# FPGA_Board_Top.net
KiCad netlist of a schematic drawn in Altium Designer
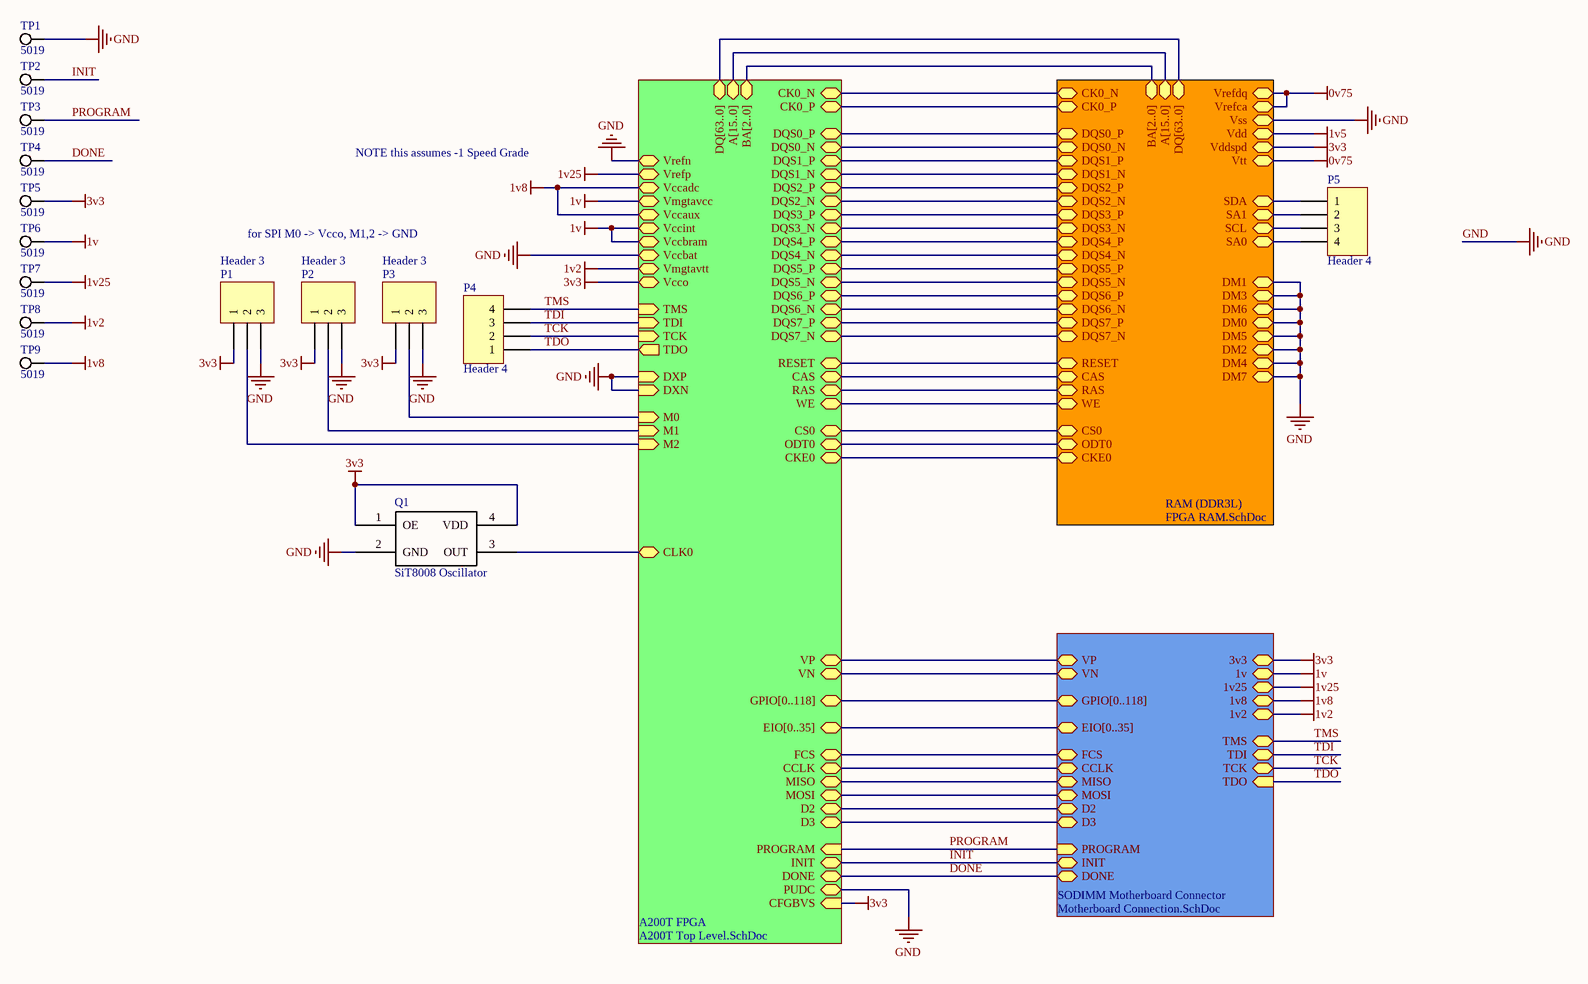
[diagram p0: FPGA Board Top.SchDoc]

(export (version "E")
  (design (tool "Eeschema 10.0.6"))
  (components
    (comp (ref "P1")
      (value "Header 3")
      (footprint "HDR1X3")
      (description "Header, 3-Pin")
      (fields (field (name "PUBLISHER") "Altium Limited"))
      (libsource (lib "Miscellaneous Connectors") (part "Header 3"))
    )
    (comp (ref "P2")
      (value "Header 3")
      (footprint "HDR1X3")
      (description "Header, 3-Pin")
      (fields (field (name "PUBLISHER") "Altium Limited"))
      (libsource (lib "Miscellaneous Connectors") (part "Header 3"))
    )
    (comp (ref "P3")
      (value "Header 3")
      (footprint "HDR1X3")
      (description "Header, 3-Pin")
      (fields (field (name "PUBLISHER") "Altium Limited"))
      (libsource (lib "Miscellaneous Connectors") (part "Header 3"))
    )
    (comp (ref "P4")
      (value "Header 4")
      (footprint "HDR1X4")
      (description "Header, 4-Pin")
      (fields (field (name "PUBLISHER") "Altium Limited"))
      (libsource (lib "Miscellaneous Connectors") (part "Header 4"))
    )
    (comp (ref "P5")
      (value "Header 4")
      (footprint "HDR1X4")
      (description "Header, 4-Pin")
      (fields (field (name "PUBLISHER") "Altium Limited"))
      (libsource (lib "") (part "Header 4_1"))
    )
    (comp (ref "Q1")
      (value "SiT8008 Oscillator")
      (footprint "SiT8008 2.5x2")
      (libsource (lib "2020-09-26_17-27-19") (part "SiT8008 Oscillator"))
    )
    (comp (ref "TP1")
      (value "5019")
      (footprint "KSTN-5019_V")
      (description "Test Point, 1 Position SMD, RoHS, Tape and Reel")
      (libsource (lib "Altium Content Vault") (part "TESTPOINT_WHITE"))
    )
    (comp (ref "TP2")
      (value "5019")
      (footprint "KSTN-5019_V")
      (description "Test Point, 1 Position SMD, RoHS, Tape and Reel")
      (libsource (lib "Altium Content Vault") (part "TESTPOINT_WHITE"))
    )
    (comp (ref "TP3")
      (value "5019")
      (footprint "KSTN-5019_V")
      (description "Test Point, 1 Position SMD, RoHS, Tape and Reel")
      (libsource (lib "Altium Content Vault") (part "TESTPOINT_WHITE"))
    )
    (comp (ref "TP4")
      (value "5019")
      (footprint "KSTN-5019_V")
      (description "Test Point, 1 Position SMD, RoHS, Tape and Reel")
      (libsource (lib "Altium Content Vault") (part "TESTPOINT_WHITE"))
    )
    (comp (ref "TP5")
      (value "5019")
      (footprint "KSTN-5019_V")
      (description "Test Point, 1 Position SMD, RoHS, Tape and Reel")
      (libsource (lib "Altium Content Vault") (part "TESTPOINT_WHITE"))
    )
    (comp (ref "TP6")
      (value "5019")
      (footprint "KSTN-5019_V")
      (description "Test Point, 1 Position SMD, RoHS, Tape and Reel")
      (libsource (lib "Altium Content Vault") (part "TESTPOINT_WHITE"))
    )
    (comp (ref "TP7")
      (value "5019")
      (footprint "KSTN-5019_V")
      (description "Test Point, 1 Position SMD, RoHS, Tape and Reel")
      (libsource (lib "Altium Content Vault") (part "TESTPOINT_WHITE"))
    )
    (comp (ref "TP8")
      (value "5019")
      (footprint "KSTN-5019_V")
      (description "Test Point, 1 Position SMD, RoHS, Tape and Reel")
      (libsource (lib "Altium Content Vault") (part "TESTPOINT_WHITE"))
    )
    (comp (ref "TP9")
      (value "5019")
      (footprint "KSTN-5019_V")
      (description "Test Point, 1 Position SMD, RoHS, Tape and Reel")
      (libsource (lib "Altium Content Vault") (part "TESTPOINT_WHITE"))
    )
  )
  (nets
    (net (code "8") (name "/CLK0") (class "Default")
      (node (ref "Q1") (pin "3") (pinfunction "OUT_3") (pintype "passive"))
    )
    (net (code "12") (name "/DONE") (class "Default")
      (node (ref "TP4") (pin "1") (pinfunction "1_1") (pintype "passive"))
    )
    (net (code "33") (name "/INIT") (class "Default")
      (node (ref "TP2") (pin "1") (pinfunction "1_1") (pintype "passive"))
    )
    (net (code "34") (name "/M0") (class "Default")
      (node (ref "P3") (pin "2") (pinfunction "2_2") (pintype "passive"))
    )
    (net (code "35") (name "/M1") (class "Default")
      (node (ref "P2") (pin "2") (pinfunction "2_2") (pintype "passive"))
    )
    (net (code "36") (name "/M2") (class "Default")
      (node (ref "P1") (pin "2") (pinfunction "2_2") (pintype "passive"))
    )
    (net (code "40") (name "/PROGRAM") (class "Default")
      (node (ref "TP3") (pin "1") (pinfunction "1_1") (pintype "passive"))
    )
    (net (code "43") (name "/SA0") (class "Default")
      (node (ref "P5") (pin "4") (pinfunction "4_4") (pintype "passive"))
    )
    (net (code "44") (name "/SA1") (class "Default")
      (node (ref "P5") (pin "2") (pinfunction "2_2") (pintype "passive"))
    )
    (net (code "45") (name "/SCL") (class "Default")
      (node (ref "P5") (pin "3") (pinfunction "3_3") (pintype "passive"))
    )
    (net (code "46") (name "/SDA") (class "Default")
      (node (ref "P5") (pin "1") (pinfunction "1_1") (pintype "passive"))
    )
    (net (code "47") (name "/TCK") (class "Default")
      (node (ref "P4") (pin "2") (pinfunction "2_2") (pintype "passive"))
    )
    (net (code "48") (name "/TDI") (class "Default")
      (node (ref "P4") (pin "3") (pinfunction "3_3") (pintype "passive"))
    )
    (net (code "49") (name "/TDO") (class "Default")
      (node (ref "P4") (pin "1") (pinfunction "1_1") (pintype "passive"))
    )
    (net (code "50") (name "/TMS") (class "Default")
      (node (ref "P4") (pin "4") (pinfunction "4_4") (pintype "passive"))
    )
    (net (code "55") (name "1v") (class "Default")
      (node (ref "TP6") (pin "1") (pinfunction "1_1") (pintype "passive"))
    )
    (net (code "56") (name "1v2") (class "Default")
      (node (ref "TP8") (pin "1") (pinfunction "1_1") (pintype "passive"))
    )
    (net (code "58") (name "1v8") (class "Default")
      (node (ref "TP9") (pin "1") (pinfunction "1_1") (pintype "passive"))
    )
    (net (code "59") (name "1v25") (class "Default")
      (node (ref "TP7") (pin "1") (pinfunction "1_1") (pintype "passive"))
    )
    (net (code "60") (name "3v3") (class "Default")
      (node (ref "P1") (pin "1") (pinfunction "1_1") (pintype "passive"))
      (node (ref "P2") (pin "1") (pinfunction "1_1") (pintype "passive"))
      (node (ref "P3") (pin "1") (pinfunction "1_1") (pintype "passive"))
      (node (ref "Q1") (pin "1") (pinfunction "OE_1") (pintype "passive"))
      (node (ref "Q1") (pin "4") (pinfunction "VDD_4") (pintype "passive"))
      (node (ref "TP5") (pin "1") (pinfunction "1_1") (pintype "passive"))
    )
    (net (code "61") (name "GND") (class "Default")
      (node (ref "P1") (pin "3") (pinfunction "3_3") (pintype "passive"))
      (node (ref "P2") (pin "3") (pinfunction "3_3") (pintype "passive"))
      (node (ref "P3") (pin "3") (pinfunction "3_3") (pintype "passive"))
      (node (ref "Q1") (pin "2") (pinfunction "GND_2") (pintype "passive"))
      (node (ref "TP1") (pin "1") (pinfunction "1_1") (pintype "passive"))
    )
  )
)
